# Bluetooth.net
KiCad netlist of a schematic drawn in Altium Designer
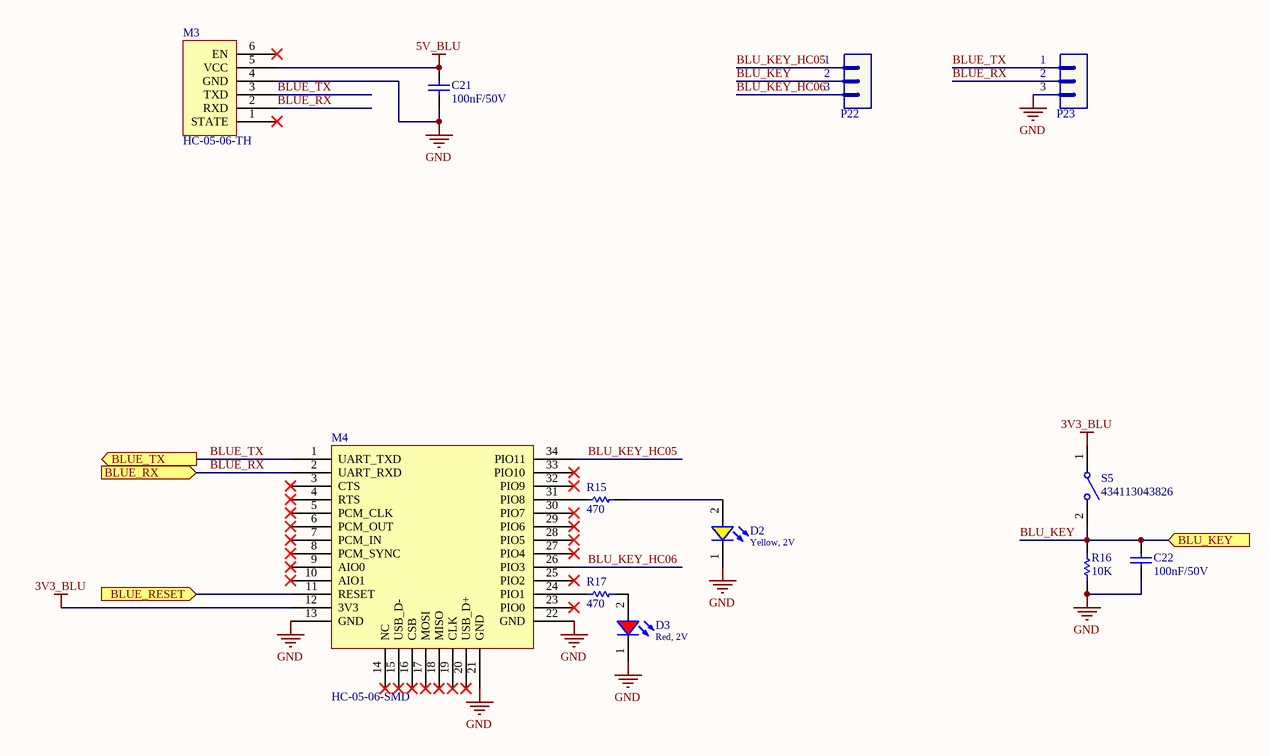
[diagram p0: Bluetooth.SchDoc]

(export (version "E")
  (design (tool "Eeschema 10.0.6"))
  (components
    (comp (ref "C21")
      (value "100nF/50V")
      (footprint "CAP-SM-0805")
      (description "CAP CER 0.1UF 50V Y5V 0805")
      (fields
        (field (name "MANUFACTURER") "Samsung Electro-Mechanics")
        (field (name "MANUFACTURER PART NUMBER") "CL21F104ZBCNNNC")
      )
      (libsource (lib "Capacitor") (part "Cap-100nF-50V-0805"))
    )
    (comp (ref "C22")
      (value "100nF/50V")
      (footprint "CAP-SM-0805")
      (description "CAP CER 0.1UF 50V Y5V 0805")
      (fields
        (field (name "MANUFACTURER") "Samsung Electro-Mechanics")
        (field (name "MANUFACTURER PART NUMBER") "CL21F104ZBCNNNC")
      )
      (libsource (lib "Capacitor") (part "Cap-100nF-50V-0805"))
    )
    (comp (ref "D2")
      (value "Yellow, 2V")
      (footprint "WL-SMCW_0805")
      (description "WL-SMCW SMT Mono-color Chip LED Waterclear, size 0805, Yellow, 2V, 140deg")
      (fields (field (name "PART NUMBER") "150080YS75000") (field (name "PUBLISHER") "Wurth Elektronik"))
      (libsource (lib "LED_150060BS75000_Altium_WL-SMCW_rev20a") (part "150080YS75000"))
    )
    (comp (ref "D3")
      (value "Red, 2V")
      (footprint "WL-SMCW_0805")
      (description "WL-SMCW SMT Mono-color Chip LED Waterclear, size 0805, Red, 2V, 140deg")
      (fields (field (name "PART NUMBER") "150080RS75000") (field (name "PUBLISHER") "Wurth Elektronik"))
      (libsource (lib "LED_150060BS75000_Altium_WL-SMCW_rev20a") (part "150080RS75000"))
    )
    (comp (ref "M3")
      (value "HC-05-06-TH")
      (footprint "HC-05-06-TH")
      (fields (field (name "LOCAL SUPPLIER PART NUMBER") "HS000882"))
      (libsource (lib "PIFWRoBot") (part "HC-05-06-TH"))
    )
    (comp (ref "M4")
      (value "HC-05-06-SMD")
      (footprint "HC-05-06-SMD")
      (fields (field (name "LOCAL SUPPLIER PART NUMBER") "HS000881"))
      (libsource (lib "PIFWRoBot") (part "HC-05-06-SMD"))
    )
    (comp (ref "P22")
      (value "Header 3")
      (footprint "JP3")
      (description "Header, 3-Pin")
      (fields (field (name "PUBLISHER") "Altium Limited"))
      (libsource (lib "Header-connector") (part "Header 3"))
    )
    (comp (ref "P23")
      (value "Header 3")
      (footprint "JP3")
      (description "Header, 3-Pin")
      (fields (field (name "PUBLISHER") "Altium Limited"))
      (libsource (lib "Header-connector") (part "Header 3"))
    )
    (comp (ref "R15")
      (value "470")
      (footprint "Resistor:RES-SM-0805")
      (description "RES 470 OHM JUMPER 0805")
      (fields
        (field (name "MANUFACTURER") "YAG6006CT-ND")
        (field (name "MANUFACTURER PART NUMBER") "PE0805FRF7W0R047L")
      )
      (libsource (lib "Resistor") (part "Res-470-0805"))
    )
    (comp (ref "R16")
      (value "10K")
      (footprint "Resistor:RES-SM-0805")
      (description "RES 10K OHM 1% 1/4W 0805")
      (fields
        (field (name "MANUFACTURER") "Stackpole Electronics Inc")
        (field (name "MANUFACTURER PART NUMBER") "RNCP0805FTD10K0")
      )
      (libsource (lib "Resistor") (part "Res-10k-0805"))
    )
    (comp (ref "R17")
      (value "470")
      (footprint "Resistor:RES-SM-0805")
      (description "RES 470 OHM JUMPER 0805")
      (fields
        (field (name "MANUFACTURER") "YAG6006CT-ND")
        (field (name "MANUFACTURER PART NUMBER") "PE0805FRF7W0R047L")
      )
      (libsource (lib "Resistor") (part "Res-470-0805"))
    )
    (comp (ref "S5")
      (value "434113043826")
      (footprint "434113043826")
      (description "WS-TASV J-Bend SMT Tact Switch 6x3.5mm, height 4.3mm, 260gf")
      (fields (field (name "PUBLISHER") "Wurth Elektronik"))
      (libsource (lib "434113043826_Altium_WS-TASV_rev20a") (part "434113043826"))
    )
  )
  (nets
    (net (code "1") (name "/BLUE_RESET") (class "Default")
      (node (ref "M4") (pin "11") (pinfunction "RESET_11") (pintype "passive"))
    )
    (net (code "2") (name "/BLUE_RX") (class "Default")
      (node (ref "M3") (pin "2") (pinfunction "RXD_2") (pintype "passive"))
      (node (ref "M4") (pin "2") (pinfunction "UART_RXD_2") (pintype "passive"))
      (node (ref "P23") (pin "2") (pinfunction "2_2") (pintype "passive"))
    )
    (net (code "3") (name "/BLUE_TX") (class "Default")
      (node (ref "M3") (pin "3") (pinfunction "TXD_3") (pintype "passive"))
      (node (ref "M4") (pin "1") (pinfunction "UART_TXD_1") (pintype "passive"))
      (node (ref "P23") (pin "1") (pinfunction "1_1") (pintype "passive"))
    )
    (net (code "4") (name "/BLU_KEY") (class "Default")
      (node (ref "C22") (pin "2") (pinfunction "2_2") (pintype "passive"))
      (node (ref "P22") (pin "2") (pinfunction "2_2") (pintype "passive"))
      (node (ref "R16") (pin "2") (pinfunction "2_2") (pintype "passive"))
      (node (ref "S5") (pin "2") (pinfunction "2_2") (pintype "passive"))
    )
    (net (code "5") (name "/BLU_KEY_HC05") (class "Default")
      (node (ref "M4") (pin "34") (pinfunction "PIO11_34") (pintype "passive"))
      (node (ref "P22") (pin "1") (pinfunction "1_1") (pintype "passive"))
    )
    (net (code "6") (name "/BLU_KEY_HC06") (class "Default")
      (node (ref "M4") (pin "26") (pinfunction "PIO3_26") (pintype "passive"))
      (node (ref "P22") (pin "3") (pinfunction "3_3") (pintype "passive"))
    )
    (net (code "7") (name "3V3_BLU") (class "Default")
      (node (ref "M4") (pin "12") (pinfunction "3V3_12") (pintype "passive"))
      (node (ref "S5") (pin "1") (pinfunction "1_1") (pintype "passive"))
    )
    (net (code "8") (name "5V_BLU") (class "Default")
      (node (ref "C21") (pin "2") (pinfunction "2_2") (pintype "passive"))
      (node (ref "M3") (pin "5") (pinfunction "VCC_5") (pintype "passive"))
    )
    (net (code "9") (name "GND") (class "Default")
      (node (ref "C21") (pin "1") (pinfunction "1_1") (pintype "passive"))
      (node (ref "C22") (pin "1") (pinfunction "1_1") (pintype "passive"))
      (node (ref "D2") (pin "1") (pinfunction "K_1") (pintype "passive"))
      (node (ref "D3") (pin "1") (pinfunction "K_1") (pintype "passive"))
      (node (ref "M3") (pin "4") (pinfunction "GND_4") (pintype "passive"))
      (node (ref "M4") (pin "13") (pinfunction "GND_13") (pintype "passive"))
      (node (ref "M4") (pin "21") (pinfunction "GND_21") (pintype "passive"))
      (node (ref "M4") (pin "22") (pinfunction "GND_22") (pintype "passive"))
      (node (ref "P23") (pin "3") (pinfunction "3_3") (pintype "passive"))
      (node (ref "R16") (pin "1") (pinfunction "1_1") (pintype "passive"))
    )
    (net (code "10") (name "Net-(D2-A)") (class "Default")
      (node (ref "D2") (pin "2") (pinfunction "A_2") (pintype "passive"))
      (node (ref "R15") (pin "2") (pinfunction "2_2") (pintype "passive"))
    )
    (net (code "11") (name "Net-(D3-A)") (class "Default")
      (node (ref "D3") (pin "2") (pinfunction "A_2") (pintype "passive"))
      (node (ref "R17") (pin "2") (pinfunction "2_2") (pintype "passive"))
    )
    (net (code "12") (name "Net-(M4-PIO1)") (class "Default")
      (node (ref "M4") (pin "24") (pinfunction "PIO1_24") (pintype "passive"))
      (node (ref "R17") (pin "1") (pinfunction "1_1") (pintype "passive"))
    )
    (net (code "13") (name "Net-(M4-PIO8)") (class "Default")
      (node (ref "M4") (pin "31") (pinfunction "PIO8_31") (pintype "passive"))
      (node (ref "R15") (pin "1") (pinfunction "1_1") (pintype "passive"))
    )
    (net (code "14") (name "unconnected-(M3-EN-Pad6)") (class "Default")
      (node (ref "M3") (pin "6") (pinfunction "EN_6") (pintype "passive+no_connect"))
    )
    (net (code "15") (name "unconnected-(M3-STATE-Pad1)") (class "Default")
      (node (ref "M3") (pin "1") (pinfunction "STATE_1") (pintype "passive+no_connect"))
    )
    (net (code "16") (name "unconnected-(M4-AIO0-Pad9)") (class "Default")
      (node (ref "M4") (pin "9") (pinfunction "AIO0_9") (pintype "passive+no_connect"))
    )
    (net (code "17") (name "unconnected-(M4-AIO1-Pad10)") (class "Default")
      (node (ref "M4") (pin "10") (pinfunction "AIO1_10") (pintype "passive+no_connect"))
    )
    (net (code "18") (name "unconnected-(M4-CLK-Pad19)") (class "Default")
      (node (ref "M4") (pin "19") (pinfunction "CLK_19") (pintype "passive+no_connect"))
    )
    (net (code "19") (name "unconnected-(M4-CSB-Pad16)") (class "Default")
      (node (ref "M4") (pin "16") (pinfunction "CSB_16") (pintype "passive+no_connect"))
    )
    (net (code "20") (name "unconnected-(M4-CTS-Pad3)") (class "Default")
      (node (ref "M4") (pin "3") (pinfunction "CTS_3") (pintype "passive+no_connect"))
    )
    (net (code "21") (name "unconnected-(M4-MISO-Pad18)") (class "Default")
      (node (ref "M4") (pin "18") (pinfunction "MISO_18") (pintype "passive+no_connect"))
    )
    (net (code "22") (name "unconnected-(M4-MOSI-Pad17)") (class "Default")
      (node (ref "M4") (pin "17") (pinfunction "MOSI_17") (pintype "passive+no_connect"))
    )
    (net (code "23") (name "unconnected-(M4-NC-Pad14)") (class "Default")
      (node (ref "M4") (pin "14") (pinfunction "NC_14") (pintype "passive+no_connect"))
    )
    (net (code "24") (name "unconnected-(M4-PCM_CLK-Pad5)") (class "Default")
      (node (ref "M4") (pin "5") (pinfunction "PCM_CLK_5") (pintype "passive+no_connect"))
    )
    (net (code "25") (name "unconnected-(M4-PCM_IN-Pad7)") (class "Default")
      (node (ref "M4") (pin "7") (pinfunction "PCM_IN_7") (pintype "passive+no_connect"))
    )
    (net (code "26") (name "unconnected-(M4-PCM_OUT-Pad6)") (class "Default")
      (node (ref "M4") (pin "6") (pinfunction "PCM_OUT_6") (pintype "passive+no_connect"))
    )
    (net (code "27") (name "unconnected-(M4-PCM_SYNC-Pad8)") (class "Default")
      (node (ref "M4") (pin "8") (pinfunction "PCM_SYNC_8") (pintype "passive+no_connect"))
    )
    (net (code "28") (name "unconnected-(M4-PIO0-Pad23)") (class "Default")
      (node (ref "M4") (pin "23") (pinfunction "PIO0_23") (pintype "passive+no_connect"))
    )
    (net (code "29") (name "unconnected-(M4-PIO2-Pad25)") (class "Default")
      (node (ref "M4") (pin "25") (pinfunction "PIO2_25") (pintype "passive+no_connect"))
    )
    (net (code "30") (name "unconnected-(M4-PIO4-Pad27)") (class "Default")
      (node (ref "M4") (pin "27") (pinfunction "PIO4_27") (pintype "passive+no_connect"))
    )
    (net (code "31") (name "unconnected-(M4-PIO5-Pad28)") (class "Default")
      (node (ref "M4") (pin "28") (pinfunction "PIO5_28") (pintype "passive+no_connect"))
    )
    (net (code "32") (name "unconnected-(M4-PIO6-Pad29)") (class "Default")
      (node (ref "M4") (pin "29") (pinfunction "PIO6_29") (pintype "passive+no_connect"))
    )
    (net (code "33") (name "unconnected-(M4-PIO7-Pad30)") (class "Default")
      (node (ref "M4") (pin "30") (pinfunction "PIO7_30") (pintype "passive+no_connect"))
    )
    (net (code "34") (name "unconnected-(M4-PIO9-Pad32)") (class "Default")
      (node (ref "M4") (pin "32") (pinfunction "PIO9_32") (pintype "passive+no_connect"))
    )
    (net (code "35") (name "unconnected-(M4-PIO10-Pad33)") (class "Default")
      (node (ref "M4") (pin "33") (pinfunction "PIO10_33") (pintype "passive+no_connect"))
    )
    (net (code "36") (name "unconnected-(M4-RTS-Pad4)") (class "Default")
      (node (ref "M4") (pin "4") (pinfunction "RTS_4") (pintype "passive+no_connect"))
    )
    (net (code "37") (name "unconnected-(M4-USB_D+-Pad20)") (class "Default")
      (node (ref "M4") (pin "20") (pinfunction "USB_D+_20") (pintype "passive+no_connect"))
    )
    (net (code "38") (name "unconnected-(M4-USB_D--Pad15)") (class "Default")
      (node (ref "M4") (pin "15") (pinfunction "USB_D-_15") (pintype "passive+no_connect"))
    )
  )
)
